# SparkFun_Soil_Moisture_Sensor.net
KiCad netlist of a schematic drawn in EAGLE
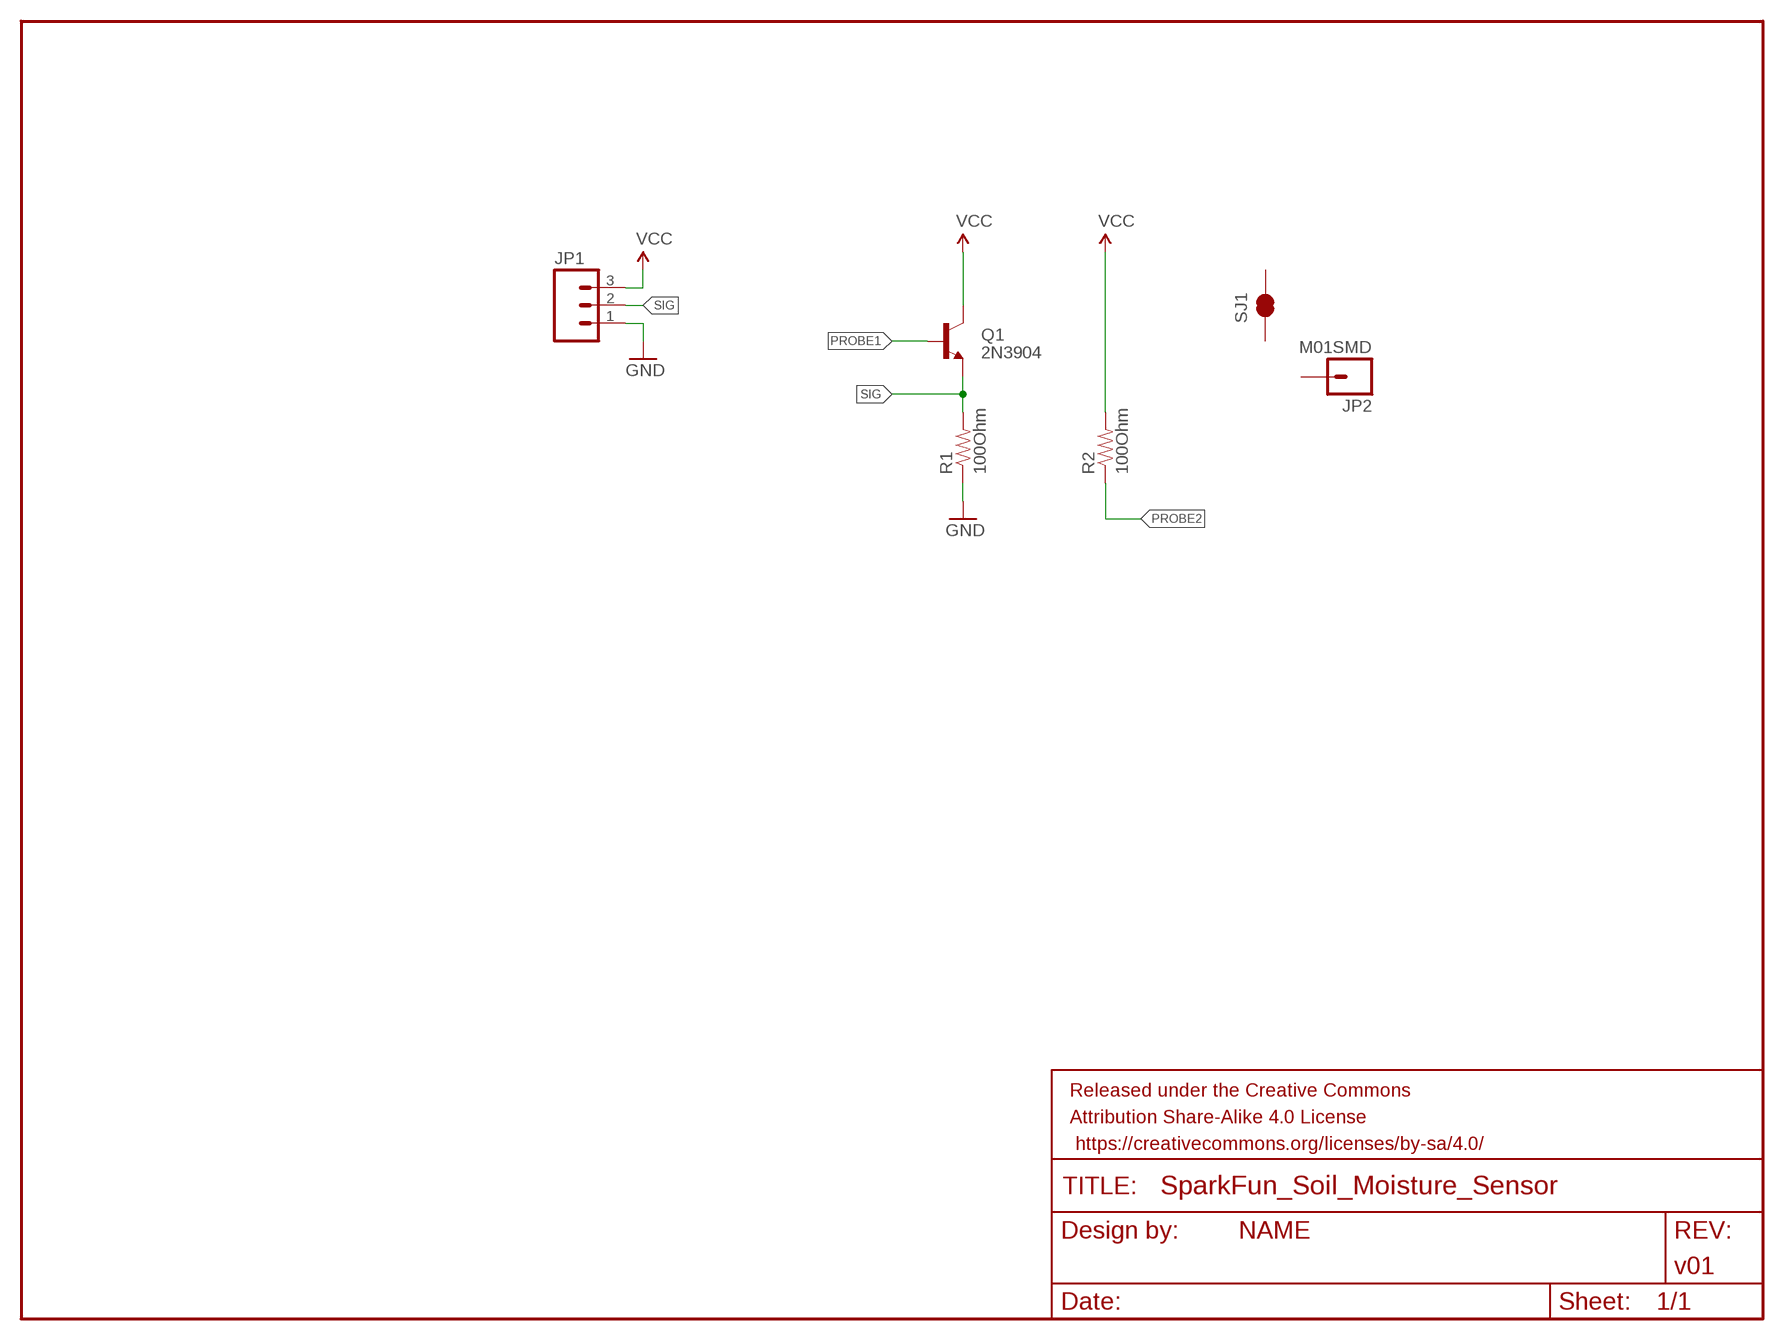
[diagram p0: schematic, sheet 1]

(export (version "E")
  (design (tool "Eeschema 10.0.6"))
  (components
    (comp (ref "FRAME1")
      (value "FRAME-LETTER")
      (footprint "eagle-import:CREATIVE_COMMONS")
      (fields (field (name "DESIGNER") "NAME"))
      (libsource (lib "eagle-import") (part "FRAME-LETTER"))
    )
    (comp (ref "JP1")
      (value "M03PTH")
      (footprint "eagle-import:1X03")
      (libsource (lib "eagle-import") (part "M03PTH"))
    )
    (comp (ref "JP2")
      (value "M01SMD")
      (footprint "eagle-import:LUXEON-PAD")
      (libsource (lib "eagle-import") (part "M01SMD"))
    )
    (comp (ref "Q1")
      (value "2N3904")
      (footprint "eagle-import:SOT23-3")
      (libsource (lib "eagle-import") (part "TRANSISTOR_NPNMMBT2222A"))
    )
    (comp (ref "R1")
      (value "100Ohm")
      (footprint "eagle-import:0603-RES")
      (libsource (lib "eagle-import") (part "100OHM-1/4W-5%(0603)"))
    )
    (comp (ref "R2")
      (value "100Ohm")
      (footprint "eagle-import:0603-RES")
      (libsource (lib "eagle-import") (part "100OHM-1/4W-5%(0603)"))
    )
    (comp (ref "SJ1")
      (value "JUMPER-PAD-2-NC_BY_TRACE")
      (footprint "eagle-import:PAD-JUMPER-2-NC_BY_TRACE_YES_SILK")
      (libsource (lib "eagle-import") (part "JUMPER-PAD-2-NC_BY_TRACE"))
    )
  )
  (nets
    (net (code "1") (name "GND") (class "Default")
      (node (ref "JP1") (pin "1") (pinfunction "1_1") (pintype "passive"))
      (node (ref "R1") (pin "1") (pinfunction "1_1") (pintype "passive"))
    )
    (net (code "2") (name "PROBE1") (class "Default")
      (node (ref "Q1") (pin "1") (pinfunction "B_1") (pintype "passive"))
    )
    (net (code "3") (name "PROBE2") (class "Default")
      (node (ref "R2") (pin "1") (pinfunction "1_1") (pintype "passive"))
    )
    (net (code "4") (name "SIG") (class "Default")
      (node (ref "JP1") (pin "2") (pinfunction "2_2") (pintype "passive"))
      (node (ref "Q1") (pin "2") (pinfunction "E_2") (pintype "passive"))
      (node (ref "R1") (pin "2") (pinfunction "2_2") (pintype "passive"))
    )
    (net (code "5") (name "VCC") (class "Default")
      (node (ref "JP1") (pin "3") (pinfunction "3_3") (pintype "passive"))
      (node (ref "Q1") (pin "3") (pinfunction "C_3") (pintype "passive"))
      (node (ref "R2") (pin "2") (pinfunction "2_2") (pintype "passive"))
    )
    (net (code "6") (name "unconnected-(JP2-1-PadP$1)") (class "Default")
      (node (ref "JP2") (pin "P$1") (pinfunction "1_P$1") (pintype "passive"))
    )
    (net (code "7") (name "unconnected-(SJ1-Pad1)") (class "Default")
      (node (ref "SJ1") (pin "1") (pinfunction "1_1") (pintype "passive"))
    )
    (net (code "8") (name "unconnected-(SJ1-Pad2)") (class "Default")
      (node (ref "SJ1") (pin "2") (pinfunction "2_2") (pintype "passive"))
    )
  )
)
